# XMICRO-BREAKOUT_V1_0.net
KiCad netlist of a schematic drawn in EAGLE
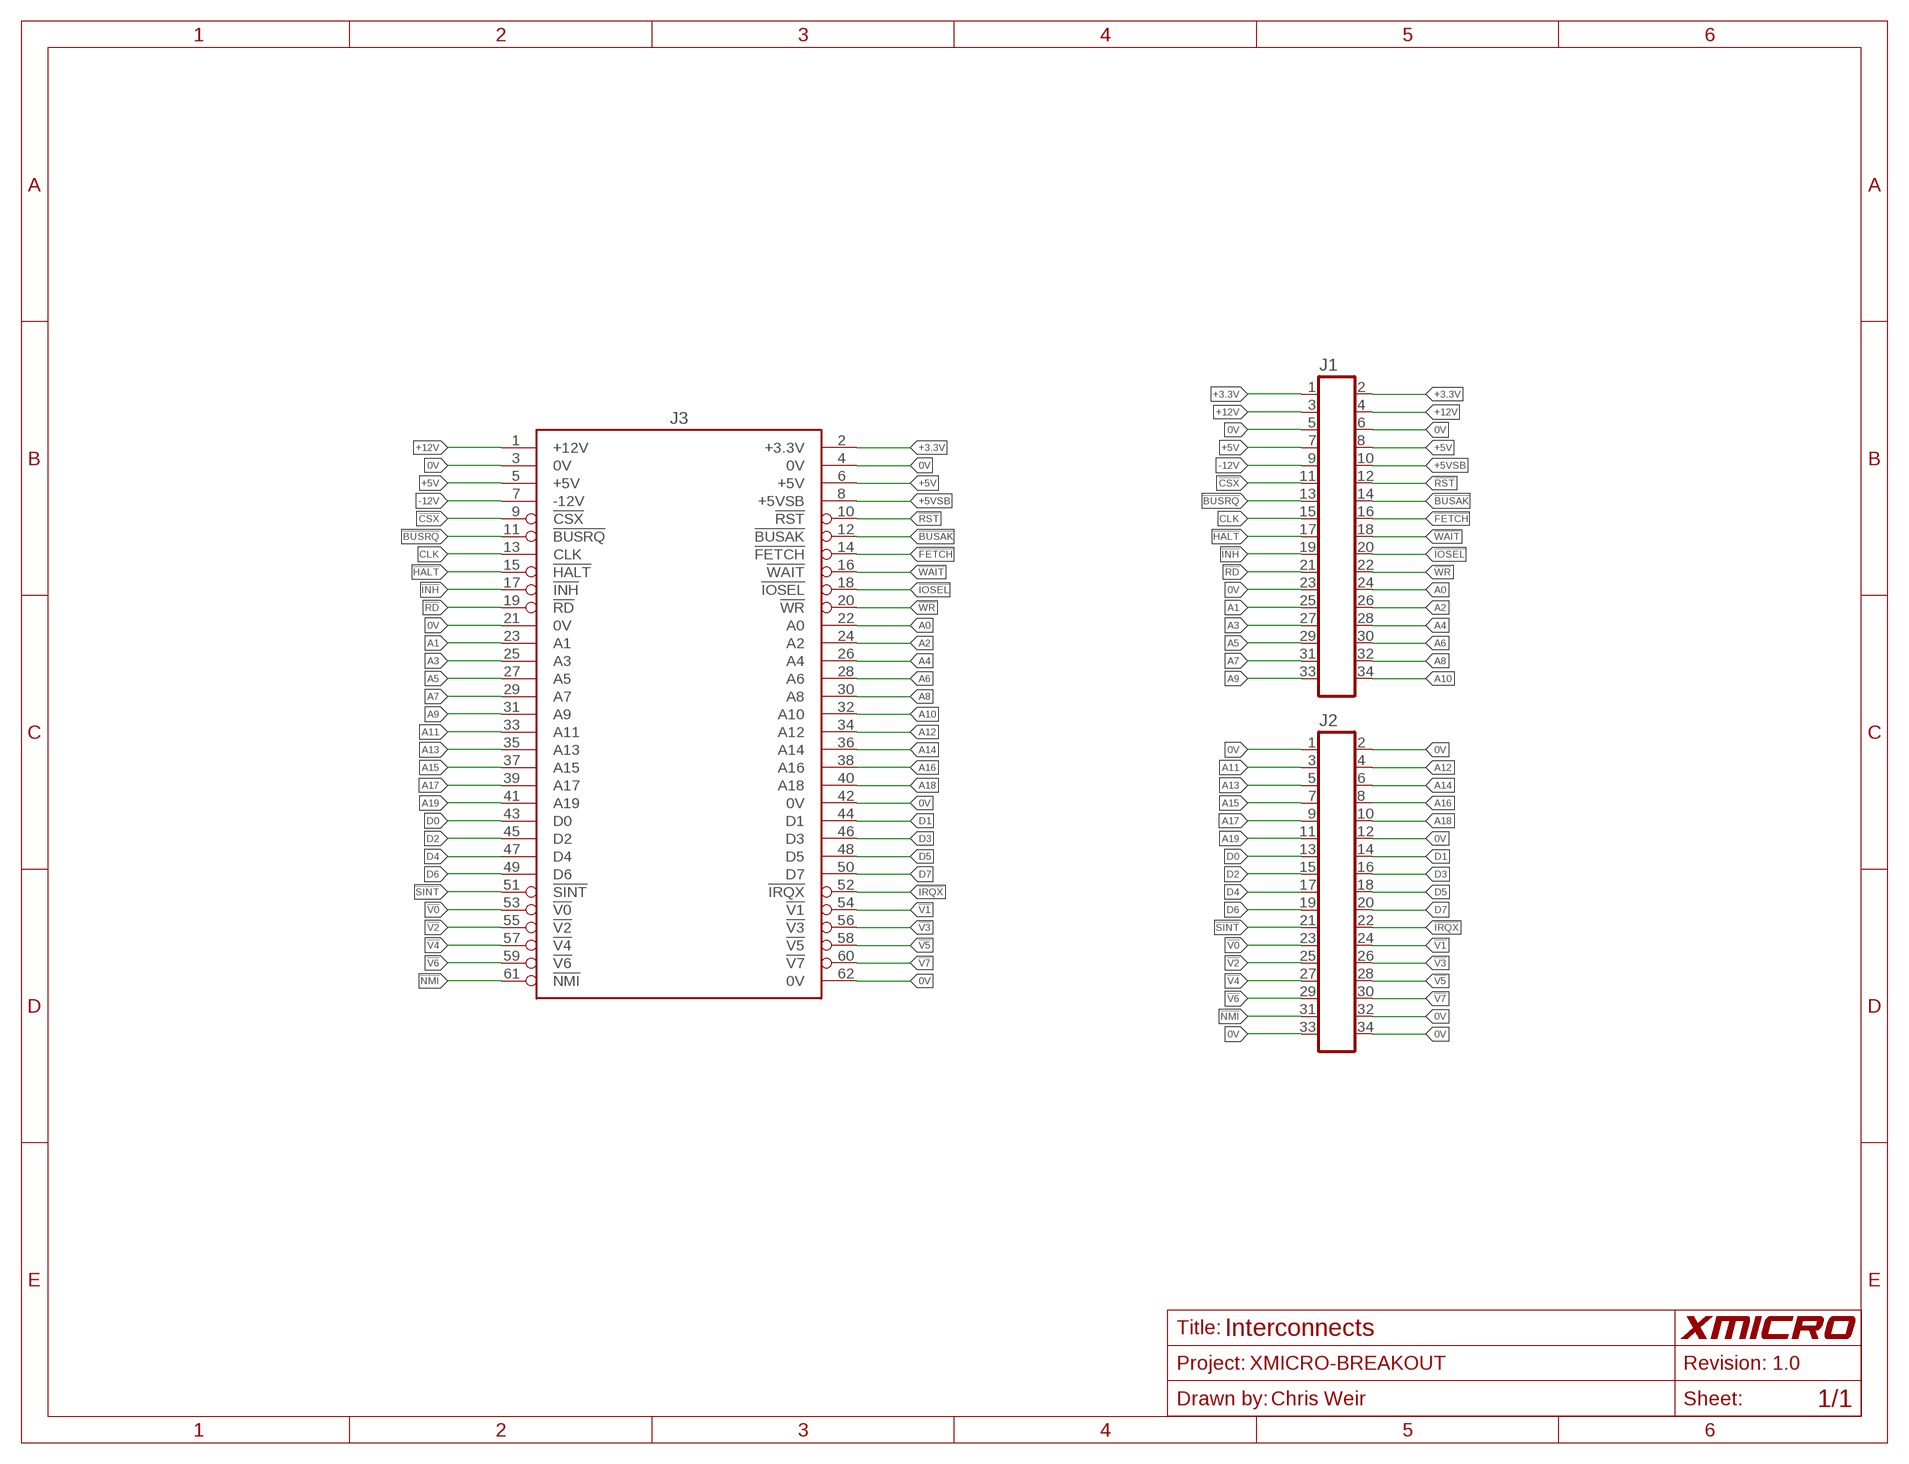
[diagram p0: schematic, sheet 1]

(export (version "E")
  (design (tool "Eeschema 10.0.6"))
  (components
    (comp (ref "J1")
      (value "HDR-17X2")
      (footprint "eagle-import:HDR-17X2S")
      (libsource (lib "eagle-import") (part "HDR-17X2"))
    )
    (comp (ref "J2")
      (value "HDR-17X2")
      (footprint "eagle-import:HDR-17X2S")
      (libsource (lib "eagle-import") (part "HDR-17X2"))
    )
    (comp (ref "J3")
      (value "XMICRO-BUS-PHYSICAL-M")
      (footprint "eagle-import:EDGE62M")
      (libsource (lib "eagle-import") (part "XMICRO-BUS-PHYSICAL-M"))
    )
  )
  (nets
    (net (code "1") (name "+3.3V") (class "Default")
      (node (ref "J1") (pin "1") (pinfunction "1_1") (pintype "passive"))
      (node (ref "J1") (pin "2") (pinfunction "2_2") (pintype "passive"))
      (node (ref "J3") (pin "2") (pinfunction "+3.3V_2") (pintype "bidirectional"))
    )
    (net (code "2") (name "+5V") (class "Default")
      (node (ref "J1") (pin "7") (pinfunction "7_7") (pintype "passive"))
      (node (ref "J1") (pin "8") (pinfunction "8_8") (pintype "passive"))
      (node (ref "J3") (pin "5") (pinfunction "+5V_5") (pintype "bidirectional"))
      (node (ref "J3") (pin "6") (pinfunction "+5V_6") (pintype "bidirectional"))
    )
    (net (code "3") (name "+5VSB") (class "Default")
      (node (ref "J1") (pin "10") (pinfunction "10_10") (pintype "passive"))
      (node (ref "J3") (pin "8") (pinfunction "+5VSB_8") (pintype "bidirectional"))
    )
    (net (code "4") (name "+12V") (class "Default")
      (node (ref "J1") (pin "3") (pinfunction "3_3") (pintype "passive"))
      (node (ref "J1") (pin "4") (pinfunction "4_4") (pintype "passive"))
      (node (ref "J3") (pin "1") (pinfunction "+12V_1") (pintype "bidirectional"))
    )
    (net (code "5") (name "-12V") (class "Default")
      (node (ref "J1") (pin "9") (pinfunction "9_9") (pintype "passive"))
      (node (ref "J3") (pin "7") (pinfunction "-12V_7") (pintype "bidirectional"))
    )
    (net (code "6") (name "/~{BUSAK}") (class "Default")
      (node (ref "J1") (pin "14") (pinfunction "14_14") (pintype "passive"))
      (node (ref "J3") (pin "12") (pinfunction "~{BUSAK}_12") (pintype "bidirectional"))
    )
    (net (code "7") (name "/~{BUSRQ}") (class "Default")
      (node (ref "J1") (pin "13") (pinfunction "13_13") (pintype "passive"))
      (node (ref "J3") (pin "11") (pinfunction "~{BUSRQ}_11") (pintype "bidirectional"))
    )
    (net (code "8") (name "/~{CSX}") (class "Default")
      (node (ref "J1") (pin "11") (pinfunction "11_11") (pintype "passive"))
      (node (ref "J3") (pin "9") (pinfunction "~{CSX}_9") (pintype "bidirectional"))
    )
    (net (code "9") (name "/~{FETCH}") (class "Default")
      (node (ref "J1") (pin "16") (pinfunction "16_16") (pintype "passive"))
      (node (ref "J3") (pin "14") (pinfunction "~{FETCH}_14") (pintype "bidirectional"))
    )
    (net (code "10") (name "/~{HALT}") (class "Default")
      (node (ref "J1") (pin "17") (pinfunction "17_17") (pintype "passive"))
      (node (ref "J3") (pin "15") (pinfunction "~{HALT}_15") (pintype "bidirectional"))
    )
    (net (code "11") (name "/~{INH}") (class "Default")
      (node (ref "J1") (pin "19") (pinfunction "19_19") (pintype "passive"))
      (node (ref "J3") (pin "17") (pinfunction "~{INH}_17") (pintype "bidirectional"))
    )
    (net (code "12") (name "/~{IOSEL}") (class "Default")
      (node (ref "J1") (pin "20") (pinfunction "20_20") (pintype "passive"))
      (node (ref "J3") (pin "18") (pinfunction "~{IOSEL}_18") (pintype "bidirectional"))
    )
    (net (code "13") (name "/~{IRQX}") (class "Default")
      (node (ref "J2") (pin "22") (pinfunction "22_22") (pintype "passive"))
      (node (ref "J3") (pin "52") (pinfunction "~{IRQX}_52") (pintype "bidirectional"))
    )
    (net (code "14") (name "/~{NMI}") (class "Default")
      (node (ref "J2") (pin "31") (pinfunction "31_31") (pintype "passive"))
      (node (ref "J3") (pin "61") (pinfunction "~{NMI}_61") (pintype "bidirectional"))
    )
    (net (code "15") (name "/~{RD}") (class "Default")
      (node (ref "J1") (pin "21") (pinfunction "21_21") (pintype "passive"))
      (node (ref "J3") (pin "19") (pinfunction "~{RD}_19") (pintype "bidirectional"))
    )
    (net (code "16") (name "/~{RST}") (class "Default")
      (node (ref "J1") (pin "12") (pinfunction "12_12") (pintype "passive"))
      (node (ref "J3") (pin "10") (pinfunction "~{RST}_10") (pintype "bidirectional"))
    )
    (net (code "17") (name "/~{SINT}") (class "Default")
      (node (ref "J2") (pin "21") (pinfunction "21_21") (pintype "passive"))
      (node (ref "J3") (pin "51") (pinfunction "~{SINT}_51") (pintype "bidirectional"))
    )
    (net (code "18") (name "/~{V0}") (class "Default")
      (node (ref "J2") (pin "23") (pinfunction "23_23") (pintype "passive"))
      (node (ref "J3") (pin "53") (pinfunction "~{V0}_53") (pintype "bidirectional"))
    )
    (net (code "19") (name "/~{V1}") (class "Default")
      (node (ref "J2") (pin "24") (pinfunction "24_24") (pintype "passive"))
      (node (ref "J3") (pin "54") (pinfunction "~{V1}_54") (pintype "bidirectional"))
    )
    (net (code "20") (name "/~{V2}") (class "Default")
      (node (ref "J2") (pin "25") (pinfunction "25_25") (pintype "passive"))
      (node (ref "J3") (pin "55") (pinfunction "~{V2}_55") (pintype "bidirectional"))
    )
    (net (code "21") (name "/~{V3}") (class "Default")
      (node (ref "J2") (pin "26") (pinfunction "26_26") (pintype "passive"))
      (node (ref "J3") (pin "56") (pinfunction "~{V3}_56") (pintype "bidirectional"))
    )
    (net (code "22") (name "/~{V4}") (class "Default")
      (node (ref "J2") (pin "27") (pinfunction "27_27") (pintype "passive"))
      (node (ref "J3") (pin "57") (pinfunction "~{V4}_57") (pintype "bidirectional"))
    )
    (net (code "23") (name "/~{V5}") (class "Default")
      (node (ref "J2") (pin "28") (pinfunction "28_28") (pintype "passive"))
      (node (ref "J3") (pin "58") (pinfunction "~{V5}_58") (pintype "bidirectional"))
    )
    (net (code "24") (name "/~{V6}") (class "Default")
      (node (ref "J2") (pin "29") (pinfunction "29_29") (pintype "passive"))
      (node (ref "J3") (pin "59") (pinfunction "~{V6}_59") (pintype "bidirectional"))
    )
    (net (code "25") (name "/~{V7}") (class "Default")
      (node (ref "J2") (pin "30") (pinfunction "30_30") (pintype "passive"))
      (node (ref "J3") (pin "60") (pinfunction "~{V7}_60") (pintype "bidirectional"))
    )
    (net (code "26") (name "/~{WAIT}") (class "Default")
      (node (ref "J1") (pin "18") (pinfunction "18_18") (pintype "passive"))
      (node (ref "J3") (pin "16") (pinfunction "~{WAIT}_16") (pintype "bidirectional"))
    )
    (net (code "27") (name "/~{WR}") (class "Default")
      (node (ref "J1") (pin "22") (pinfunction "22_22") (pintype "passive"))
      (node (ref "J3") (pin "20") (pinfunction "~{WR}_20") (pintype "bidirectional"))
    )
    (net (code "28") (name "0V") (class "Default")
      (node (ref "J1") (pin "23") (pinfunction "23_23") (pintype "passive"))
      (node (ref "J1") (pin "5") (pinfunction "5_5") (pintype "passive"))
      (node (ref "J1") (pin "6") (pinfunction "6_6") (pintype "passive"))
      (node (ref "J2") (pin "1") (pinfunction "1_1") (pintype "passive"))
      (node (ref "J2") (pin "12") (pinfunction "12_12") (pintype "passive"))
      (node (ref "J2") (pin "2") (pinfunction "2_2") (pintype "passive"))
      (node (ref "J2") (pin "32") (pinfunction "32_32") (pintype "passive"))
      (node (ref "J2") (pin "33") (pinfunction "33_33") (pintype "passive"))
      (node (ref "J2") (pin "34") (pinfunction "34_34") (pintype "passive"))
      (node (ref "J3") (pin "21") (pinfunction "0V_21") (pintype "bidirectional"))
      (node (ref "J3") (pin "3") (pinfunction "0V_3") (pintype "bidirectional"))
      (node (ref "J3") (pin "4") (pinfunction "0V_4") (pintype "bidirectional"))
      (node (ref "J3") (pin "42") (pinfunction "0V_42") (pintype "bidirectional"))
      (node (ref "J3") (pin "62") (pinfunction "0V_62") (pintype "bidirectional"))
    )
    (net (code "29") (name "A0") (class "Default")
      (node (ref "J1") (pin "24") (pinfunction "24_24") (pintype "passive"))
      (node (ref "J3") (pin "22") (pinfunction "A0_22") (pintype "bidirectional"))
    )
    (net (code "30") (name "A1") (class "Default")
      (node (ref "J1") (pin "25") (pinfunction "25_25") (pintype "passive"))
      (node (ref "J3") (pin "23") (pinfunction "A1_23") (pintype "bidirectional"))
    )
    (net (code "31") (name "A2") (class "Default")
      (node (ref "J1") (pin "26") (pinfunction "26_26") (pintype "passive"))
      (node (ref "J3") (pin "24") (pinfunction "A2_24") (pintype "bidirectional"))
    )
    (net (code "32") (name "A3") (class "Default")
      (node (ref "J1") (pin "27") (pinfunction "27_27") (pintype "passive"))
      (node (ref "J3") (pin "25") (pinfunction "A3_25") (pintype "bidirectional"))
    )
    (net (code "33") (name "A4") (class "Default")
      (node (ref "J1") (pin "28") (pinfunction "28_28") (pintype "passive"))
      (node (ref "J3") (pin "26") (pinfunction "A4_26") (pintype "bidirectional"))
    )
    (net (code "34") (name "A5") (class "Default")
      (node (ref "J1") (pin "29") (pinfunction "29_29") (pintype "passive"))
      (node (ref "J3") (pin "27") (pinfunction "A5_27") (pintype "bidirectional"))
    )
    (net (code "35") (name "A6") (class "Default")
      (node (ref "J1") (pin "30") (pinfunction "30_30") (pintype "passive"))
      (node (ref "J3") (pin "28") (pinfunction "A6_28") (pintype "bidirectional"))
    )
    (net (code "36") (name "A7") (class "Default")
      (node (ref "J1") (pin "31") (pinfunction "31_31") (pintype "passive"))
      (node (ref "J3") (pin "29") (pinfunction "A7_29") (pintype "bidirectional"))
    )
    (net (code "37") (name "A8") (class "Default")
      (node (ref "J1") (pin "32") (pinfunction "32_32") (pintype "passive"))
      (node (ref "J3") (pin "30") (pinfunction "A8_30") (pintype "bidirectional"))
    )
    (net (code "38") (name "A9") (class "Default")
      (node (ref "J1") (pin "33") (pinfunction "33_33") (pintype "passive"))
      (node (ref "J3") (pin "31") (pinfunction "A9_31") (pintype "bidirectional"))
    )
    (net (code "39") (name "A10") (class "Default")
      (node (ref "J1") (pin "34") (pinfunction "34_34") (pintype "passive"))
      (node (ref "J3") (pin "32") (pinfunction "A10_32") (pintype "bidirectional"))
    )
    (net (code "40") (name "A11") (class "Default")
      (node (ref "J2") (pin "3") (pinfunction "3_3") (pintype "passive"))
      (node (ref "J3") (pin "33") (pinfunction "A11_33") (pintype "bidirectional"))
    )
    (net (code "41") (name "A12") (class "Default")
      (node (ref "J2") (pin "4") (pinfunction "4_4") (pintype "passive"))
      (node (ref "J3") (pin "34") (pinfunction "A12_34") (pintype "bidirectional"))
    )
    (net (code "42") (name "A13") (class "Default")
      (node (ref "J2") (pin "5") (pinfunction "5_5") (pintype "passive"))
      (node (ref "J3") (pin "35") (pinfunction "A13_35") (pintype "bidirectional"))
    )
    (net (code "43") (name "A14") (class "Default")
      (node (ref "J2") (pin "6") (pinfunction "6_6") (pintype "passive"))
      (node (ref "J3") (pin "36") (pinfunction "A14_36") (pintype "bidirectional"))
    )
    (net (code "44") (name "A15") (class "Default")
      (node (ref "J2") (pin "7") (pinfunction "7_7") (pintype "passive"))
      (node (ref "J3") (pin "37") (pinfunction "A15_37") (pintype "bidirectional"))
    )
    (net (code "45") (name "A16") (class "Default")
      (node (ref "J2") (pin "8") (pinfunction "8_8") (pintype "passive"))
      (node (ref "J3") (pin "38") (pinfunction "A16_38") (pintype "bidirectional"))
    )
    (net (code "46") (name "A17") (class "Default")
      (node (ref "J2") (pin "9") (pinfunction "9_9") (pintype "passive"))
      (node (ref "J3") (pin "39") (pinfunction "A17_39") (pintype "bidirectional"))
    )
    (net (code "47") (name "A18") (class "Default")
      (node (ref "J2") (pin "10") (pinfunction "10_10") (pintype "passive"))
      (node (ref "J3") (pin "40") (pinfunction "A18_40") (pintype "bidirectional"))
    )
    (net (code "48") (name "A19") (class "Default")
      (node (ref "J2") (pin "11") (pinfunction "11_11") (pintype "passive"))
      (node (ref "J3") (pin "41") (pinfunction "A19_41") (pintype "bidirectional"))
    )
    (net (code "49") (name "CLK") (class "Default")
      (node (ref "J1") (pin "15") (pinfunction "15_15") (pintype "passive"))
      (node (ref "J3") (pin "13") (pinfunction "CLK_13") (pintype "bidirectional"))
    )
    (net (code "50") (name "D0") (class "Default")
      (node (ref "J2") (pin "13") (pinfunction "13_13") (pintype "passive"))
      (node (ref "J3") (pin "43") (pinfunction "D0_43") (pintype "bidirectional"))
    )
    (net (code "51") (name "D1") (class "Default")
      (node (ref "J2") (pin "14") (pinfunction "14_14") (pintype "passive"))
      (node (ref "J3") (pin "44") (pinfunction "D1_44") (pintype "bidirectional"))
    )
    (net (code "52") (name "D2") (class "Default")
      (node (ref "J2") (pin "15") (pinfunction "15_15") (pintype "passive"))
      (node (ref "J3") (pin "45") (pinfunction "D2_45") (pintype "bidirectional"))
    )
    (net (code "53") (name "D3") (class "Default")
      (node (ref "J2") (pin "16") (pinfunction "16_16") (pintype "passive"))
      (node (ref "J3") (pin "46") (pinfunction "D3_46") (pintype "bidirectional"))
    )
    (net (code "54") (name "D4") (class "Default")
      (node (ref "J2") (pin "17") (pinfunction "17_17") (pintype "passive"))
      (node (ref "J3") (pin "47") (pinfunction "D4_47") (pintype "bidirectional"))
    )
    (net (code "55") (name "D5") (class "Default")
      (node (ref "J2") (pin "18") (pinfunction "18_18") (pintype "passive"))
      (node (ref "J3") (pin "48") (pinfunction "D5_48") (pintype "bidirectional"))
    )
    (net (code "56") (name "D6") (class "Default")
      (node (ref "J2") (pin "19") (pinfunction "19_19") (pintype "passive"))
      (node (ref "J3") (pin "49") (pinfunction "D6_49") (pintype "bidirectional"))
    )
    (net (code "57") (name "D7") (class "Default")
      (node (ref "J2") (pin "20") (pinfunction "20_20") (pintype "passive"))
      (node (ref "J3") (pin "50") (pinfunction "D7_50") (pintype "bidirectional"))
    )
  )
)
